# LPCB223_-_CORE_INTERFACE.net
KiCad netlist of a schematic drawn in Altium Designer
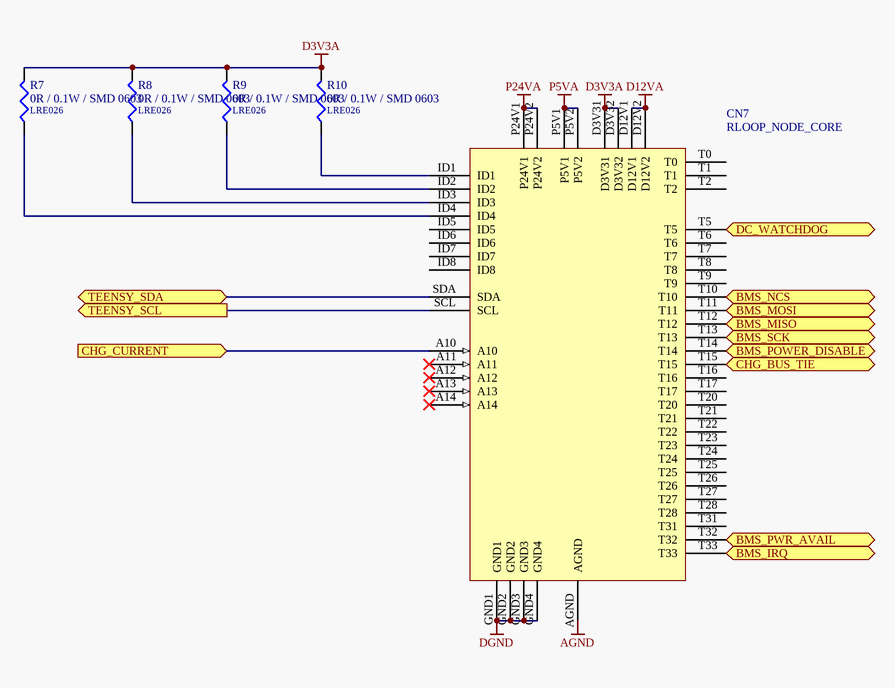
[diagram p0: LPCB223 - CORE INTERFACE.SchDoc]

(export (version "E")
  (design (tool "Eeschema 10.0.6"))
  (components
    (comp (ref "CN7")
      (value "RLOOP_NODE_CORE")
      (footprint "RLOOP_NODE_CORE")
      (description "rLoop Node Core Connector")
      (libsource (lib "LDL_Connectors") (part "RLOOP_NODE_CORE"))
    )
    (comp (ref "R7")
      (value "0R / 0.1W / SMD 0603")
      (footprint "LFP020__CR1608-0603-IPC7351_B")
      (description "Resistor, Ceramic Chip, 0R, 0.1W, SMD 0603 [LRE026]")
      (fields (field (name "LDL_NUMBER") "LRE026"))
      (libsource (lib "LDL_Resistors") (part "0R / 0.1W / SMD 0603"))
    )
    (comp (ref "R8")
      (value "0R / 0.1W / SMD 0603")
      (footprint "LFP020__CR1608-0603-IPC7351_B")
      (description "Resistor, Ceramic Chip, 0R, 0.1W, SMD 0603 [LRE026]")
      (fields (field (name "LDL_NUMBER") "LRE026"))
      (libsource (lib "LDL_Resistors") (part "0R / 0.1W / SMD 0603"))
    )
    (comp (ref "R9")
      (value "0R / 0.1W / SMD 0603")
      (footprint "LFP020__CR1608-0603-IPC7351_B")
      (description "Resistor, Ceramic Chip, 0R, 0.1W, SMD 0603 [LRE026]")
      (fields (field (name "LDL_NUMBER") "LRE026"))
      (libsource (lib "LDL_Resistors") (part "0R / 0.1W / SMD 0603"))
    )
    (comp (ref "R10")
      (value "0R / 0.1W / SMD 0603")
      (footprint "LFP020__CR1608-0603-IPC7351_B")
      (description "Resistor, Ceramic Chip, 0R, 0.1W, SMD 0603 [LRE026]")
      (fields (field (name "LDL_NUMBER") "LRE026"))
      (libsource (lib "LDL_Resistors") (part "0R / 0.1W / SMD 0603"))
    )
  )
  (nets
    (net (code "1") (name "/BMS_IRQ") (class "Default")
      (node (ref "CN7") (pin "T33") (pinfunction "T33_T33") (pintype "passive"))
    )
    (net (code "2") (name "/BMS_MISO") (class "Default")
      (node (ref "CN7") (pin "T12") (pinfunction "T12_T12") (pintype "passive"))
    )
    (net (code "3") (name "/BMS_MOSI") (class "Default")
      (node (ref "CN7") (pin "T11") (pinfunction "T11_T11") (pintype "passive"))
    )
    (net (code "4") (name "/BMS_NCS") (class "Default")
      (node (ref "CN7") (pin "T10") (pinfunction "T10_T10") (pintype "passive"))
    )
    (net (code "5") (name "/BMS_POWER_DISABLE") (class "Default")
      (node (ref "CN7") (pin "T14") (pinfunction "T14_T14") (pintype "passive"))
    )
    (net (code "6") (name "/BMS_PWR_AVAIL") (class "Default")
      (node (ref "CN7") (pin "T32") (pinfunction "T32_T32") (pintype "passive"))
    )
    (net (code "7") (name "/BMS_SCK") (class "Default")
      (node (ref "CN7") (pin "T13") (pinfunction "T13_T13") (pintype "passive"))
    )
    (net (code "8") (name "/CHG_BUS_TIE") (class "Default")
      (node (ref "CN7") (pin "T15") (pinfunction "T15_T15") (pintype "passive"))
    )
    (net (code "9") (name "/CHG_CURRENT") (class "Default")
      (node (ref "CN7") (pin "A10") (pinfunction "A10_A10") (pintype "input"))
    )
    (net (code "10") (name "/DC_WATCHDOG") (class "Default")
      (node (ref "CN7") (pin "T5") (pinfunction "T5_T5") (pintype "passive"))
    )
    (net (code "11") (name "/TEENSY_SCL") (class "Default")
      (node (ref "CN7") (pin "SCL") (pinfunction "SCL_SCL") (pintype "passive"))
    )
    (net (code "12") (name "/TEENSY_SDA") (class "Default")
      (node (ref "CN7") (pin "SDA") (pinfunction "SDA_SDA") (pintype "passive"))
    )
    (net (code "13") (name "AGND") (class "Default")
      (node (ref "CN7") (pin "AGND") (pinfunction "AGND_AGND") (pintype "power_in"))
    )
    (net (code "14") (name "D3V3A") (class "Default")
      (node (ref "CN7") (pin "D3V31") (pinfunction "D3V31_D3V31") (pintype "power_in"))
      (node (ref "CN7") (pin "D3V32") (pinfunction "D3V32_D3V32") (pintype "power_in"))
      (node (ref "R10") (pin "2") (pintype "passive"))
      (node (ref "R7") (pin "2") (pintype "passive"))
      (node (ref "R8") (pin "2") (pintype "passive"))
      (node (ref "R9") (pin "2") (pintype "passive"))
    )
    (net (code "15") (name "D12VA") (class "Default")
      (node (ref "CN7") (pin "D12V1") (pinfunction "D12V1_D12V1") (pintype "power_in"))
      (node (ref "CN7") (pin "D12V2") (pinfunction "D12V2_D12V2") (pintype "power_in"))
    )
    (net (code "16") (name "DGND") (class "Default")
      (node (ref "CN7") (pin "GND1") (pinfunction "GND1_GND1") (pintype "power_in"))
      (node (ref "CN7") (pin "GND2") (pinfunction "GND2_GND2") (pintype "power_in"))
      (node (ref "CN7") (pin "GND3") (pinfunction "GND3_GND3") (pintype "power_in"))
      (node (ref "CN7") (pin "GND4") (pinfunction "GND4_GND4") (pintype "power_in"))
    )
    (net (code "17") (name "Net-(CN7-PadID1)") (class "Default")
      (node (ref "CN7") (pin "ID1") (pinfunction "ID1_ID1") (pintype "passive"))
      (node (ref "R10") (pin "1") (pintype "passive"))
    )
    (net (code "18") (name "Net-(CN7-PadID2)") (class "Default")
      (node (ref "CN7") (pin "ID2") (pinfunction "ID2_ID2") (pintype "passive"))
      (node (ref "R9") (pin "1") (pintype "passive"))
    )
    (net (code "19") (name "Net-(CN7-PadID3)") (class "Default")
      (node (ref "CN7") (pin "ID3") (pinfunction "ID3_ID3") (pintype "passive"))
      (node (ref "R8") (pin "1") (pintype "passive"))
    )
    (net (code "20") (name "Net-(CN7-PadID4)") (class "Default")
      (node (ref "CN7") (pin "ID4") (pinfunction "ID4_ID4") (pintype "passive"))
      (node (ref "R7") (pin "1") (pintype "passive"))
    )
    (net (code "21") (name "P5VA") (class "Default")
      (node (ref "CN7") (pin "P5V1") (pinfunction "P5V1_P5V1") (pintype "power_in"))
      (node (ref "CN7") (pin "P5V2") (pinfunction "P5V2_P5V2") (pintype "power_in"))
    )
    (net (code "22") (name "P24VA") (class "Default")
      (node (ref "CN7") (pin "P24V1") (pinfunction "P24V1_P24V1") (pintype "power_in"))
      (node (ref "CN7") (pin "P24V2") (pinfunction "P24V2_P24V2") (pintype "power_in"))
    )
    (net (code "23") (name "unconnected-(CN7-PadA11)") (class "Default")
      (node (ref "CN7") (pin "A11") (pinfunction "A11_A11") (pintype "input+no_connect"))
    )
    (net (code "24") (name "unconnected-(CN7-PadA12)") (class "Default")
      (node (ref "CN7") (pin "A12") (pinfunction "A12_A12") (pintype "input+no_connect"))
    )
    (net (code "25") (name "unconnected-(CN7-PadA13)") (class "Default")
      (node (ref "CN7") (pin "A13") (pinfunction "A13_A13") (pintype "input+no_connect"))
    )
    (net (code "26") (name "unconnected-(CN7-PadA14)") (class "Default")
      (node (ref "CN7") (pin "A14") (pinfunction "A14_A14") (pintype "input+no_connect"))
    )
    (net (code "27") (name "unconnected-(CN7-PadID5)") (class "Default")
      (node (ref "CN7") (pin "ID5") (pinfunction "ID5_ID5") (pintype "passive"))
    )
    (net (code "28") (name "unconnected-(CN7-PadID6)") (class "Default")
      (node (ref "CN7") (pin "ID6") (pinfunction "ID6_ID6") (pintype "passive"))
    )
    (net (code "29") (name "unconnected-(CN7-PadID7)") (class "Default")
      (node (ref "CN7") (pin "ID7") (pinfunction "ID7_ID7") (pintype "passive"))
    )
    (net (code "30") (name "unconnected-(CN7-PadID8)") (class "Default")
      (node (ref "CN7") (pin "ID8") (pinfunction "ID8_ID8") (pintype "passive"))
    )
    (net (code "31") (name "unconnected-(CN7-PadT0)") (class "Default")
      (node (ref "CN7") (pin "T0") (pinfunction "T0_T0") (pintype "passive"))
    )
    (net (code "32") (name "unconnected-(CN7-PadT1)") (class "Default")
      (node (ref "CN7") (pin "T1") (pinfunction "T1_T1") (pintype "passive"))
    )
    (net (code "33") (name "unconnected-(CN7-PadT2)") (class "Default")
      (node (ref "CN7") (pin "T2") (pinfunction "T2_T2") (pintype "passive"))
    )
    (net (code "34") (name "unconnected-(CN7-PadT6)") (class "Default")
      (node (ref "CN7") (pin "T6") (pinfunction "T6_T6") (pintype "passive"))
    )
    (net (code "35") (name "unconnected-(CN7-PadT7)") (class "Default")
      (node (ref "CN7") (pin "T7") (pinfunction "T7_T7") (pintype "passive"))
    )
    (net (code "36") (name "unconnected-(CN7-PadT8)") (class "Default")
      (node (ref "CN7") (pin "T8") (pinfunction "T8_T8") (pintype "passive"))
    )
    (net (code "37") (name "unconnected-(CN7-PadT9)") (class "Default")
      (node (ref "CN7") (pin "T9") (pinfunction "T9_T9") (pintype "passive"))
    )
    (net (code "38") (name "unconnected-(CN7-PadT16)") (class "Default")
      (node (ref "CN7") (pin "T16") (pinfunction "T16_T16") (pintype "passive"))
    )
    (net (code "39") (name "unconnected-(CN7-PadT17)") (class "Default")
      (node (ref "CN7") (pin "T17") (pinfunction "T17_T17") (pintype "passive"))
    )
    (net (code "40") (name "unconnected-(CN7-PadT20)") (class "Default")
      (node (ref "CN7") (pin "T20") (pinfunction "T20_T20") (pintype "passive"))
    )
    (net (code "41") (name "unconnected-(CN7-PadT21)") (class "Default")
      (node (ref "CN7") (pin "T21") (pinfunction "T21_T21") (pintype "passive"))
    )
    (net (code "42") (name "unconnected-(CN7-PadT22)") (class "Default")
      (node (ref "CN7") (pin "T22") (pinfunction "T22_T22") (pintype "passive"))
    )
    (net (code "43") (name "unconnected-(CN7-PadT23)") (class "Default")
      (node (ref "CN7") (pin "T23") (pinfunction "T23_T23") (pintype "passive"))
    )
    (net (code "44") (name "unconnected-(CN7-PadT24)") (class "Default")
      (node (ref "CN7") (pin "T24") (pinfunction "T24_T24") (pintype "passive"))
    )
    (net (code "45") (name "unconnected-(CN7-PadT25)") (class "Default")
      (node (ref "CN7") (pin "T25") (pinfunction "T25_T25") (pintype "passive"))
    )
    (net (code "46") (name "unconnected-(CN7-PadT26)") (class "Default")
      (node (ref "CN7") (pin "T26") (pinfunction "T26_T26") (pintype "passive"))
    )
    (net (code "47") (name "unconnected-(CN7-PadT27)") (class "Default")
      (node (ref "CN7") (pin "T27") (pinfunction "T27_T27") (pintype "passive"))
    )
    (net (code "48") (name "unconnected-(CN7-PadT28)") (class "Default")
      (node (ref "CN7") (pin "T28") (pinfunction "T28_T28") (pintype "passive"))
    )
    (net (code "49") (name "unconnected-(CN7-PadT31)") (class "Default")
      (node (ref "CN7") (pin "T31") (pinfunction "T31_T31") (pintype "passive"))
    )
  )
)
